# LCD_i2c_Encoder.net
KiCad netlist of a schematic drawn in EAGLE
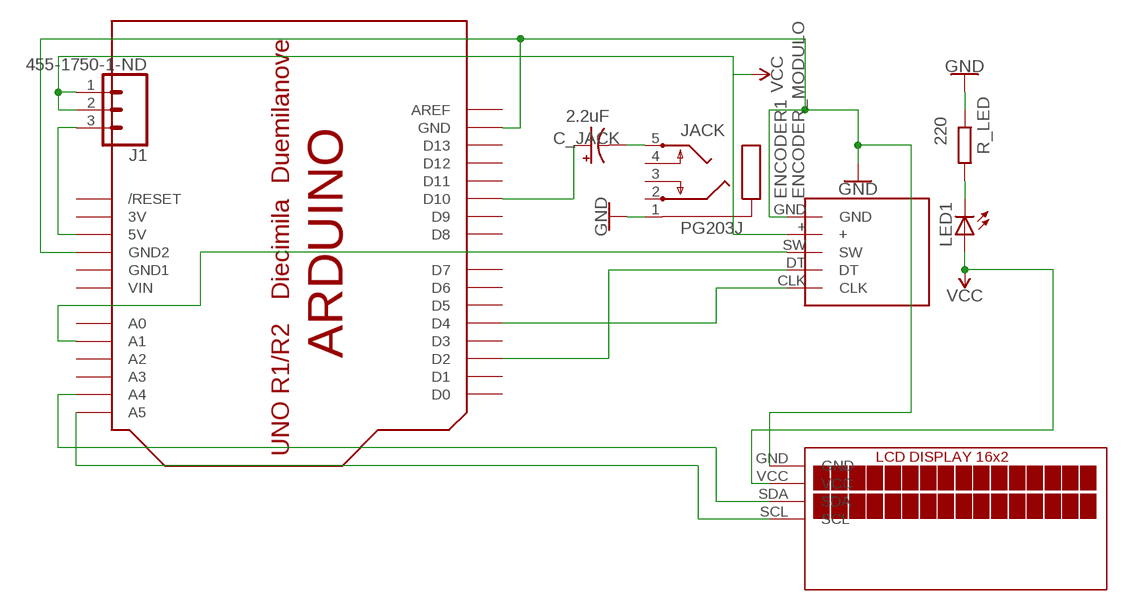
[diagram p0: schematic, sheet 1]

(export (version "E")
  (design (tool "Eeschema 10.0.6"))
  (components
    (comp (ref "C_JACK")
      (value "CPOL-USE2,5-6E")
      (footprint "eagle-import:E2,5-6E")
      (fields (field (name "CAPACITANCIA") "2.2uF"))
      (libsource (lib "eagle-import") (part "CPOL-USE2,5-6E"))
    )
    (comp (ref "ENCODER1")
      (value "ENCODER_MODULO")
      (footprint "eagle-import:ENCODER_MODULO")
      (libsource (lib "eagle-import") (part "ENCODER_MODULO"))
    )
    (comp (ref "J1")
      (value "455-1750-1-ND")
      (footprint "eagle-import:1X03")
      (libsource (lib "eagle-import") (part "CONN_03"))
    )
    (comp (ref "JACK")
      (value "PG203J")
      (footprint "eagle-import:PG203J")
      (libsource (lib "eagle-import") (part "PG203J"))
    )
    (comp (ref "LCD1")
      (value "LCDI2C")
      (footprint "eagle-import:TUXGR_16X2_R2")
      (libsource (lib "eagle-import") (part "LCDI2C"))
    )
    (comp (ref "LED1")
      (value "LED5MM")
      (footprint "eagle-import:LED5MM")
      (libsource (lib "eagle-import") (part "LED5MM"))
    )
    (comp (ref "R_LED")
      (value "R-EU_0204/7")
      (footprint "eagle-import:0204_7")
      (fields (field (name "RESISTENCIA") "220"))
      (libsource (lib "eagle-import") (part "R-EU_0204/7"))
    )
    (comp (ref "U$1")
      (value "ARDUINOUNO")
      (footprint "eagle-import:ARDUINO")
      (libsource (lib "eagle-import") (part "ARDUINOUNO"))
    )
  )
  (nets
    (net (code "1") (name "/3V") (class "Default")
      (node (ref "U$1") (pin "3V") (pinfunction "3V_3V") (pintype "power_in"))
    )
    (net (code "2") (name "/GND1") (class "Default")
      (node (ref "U$1") (pin "GND1") (pinfunction "GND1_GND1") (pintype "power_in"))
    )
    (net (code "3") (name "/VIN") (class "Default")
      (node (ref "U$1") (pin "VIN") (pinfunction "VIN_VIN") (pintype "power_in"))
    )
    (net (code "4") (name "GND") (class "Default")
      (node (ref "ENCODER1") (pin "GND") (pinfunction "GND_GND") (pintype "bidirectional"))
      (node (ref "JACK") (pin "1") (pinfunction "1_1") (pintype "passive"))
      (node (ref "LCD1") (pin "GND") (pinfunction "GND_GND") (pintype "bidirectional"))
      (node (ref "R_LED") (pin "2") (pinfunction "2_2") (pintype "passive"))
      (node (ref "U$1") (pin "GND") (pinfunction "GND_GND") (pintype "power_in"))
      (node (ref "U$1") (pin "GND2") (pinfunction "GND2_GND2") (pintype "power_in"))
    )
    (net (code "5") (name "Net-(C_JACK-Pad+)") (class "Default")
      (node (ref "C_JACK") (pin "+") (pinfunction "+_+") (pintype "passive"))
      (node (ref "U$1") (pin "D10") (pinfunction "D10_D10") (pintype "bidirectional"))
    )
    (net (code "6") (name "Net-(C_JACK-Pad-)") (class "Default")
      (node (ref "C_JACK") (pin "-") (pinfunction "-_-") (pintype "passive"))
      (node (ref "JACK") (pin "5") (pinfunction "5_5") (pintype "passive"))
    )
    (net (code "7") (name "Net-(ENCODER1-PadCLK)") (class "Default")
      (node (ref "ENCODER1") (pin "CLK") (pinfunction "CLK_CLK") (pintype "bidirectional"))
      (node (ref "U$1") (pin "D4") (pinfunction "D4_D4") (pintype "bidirectional"))
    )
    (net (code "8") (name "Net-(ENCODER1-PadDT)") (class "Default")
      (node (ref "ENCODER1") (pin "DT") (pinfunction "DT_DT") (pintype "bidirectional"))
      (node (ref "U$1") (pin "D2") (pinfunction "D2_D2") (pintype "bidirectional"))
    )
    (net (code "9") (name "Net-(ENCODER1-PadSW)") (class "Default")
      (node (ref "ENCODER1") (pin "SW") (pinfunction "SW_SW") (pintype "bidirectional"))
      (node (ref "U$1") (pin "A1") (pinfunction "A1_A1") (pintype "bidirectional"))
    )
    (net (code "10") (name "Net-(J1-Pad3)") (class "Default")
      (node (ref "J1") (pin "3") (pinfunction "3_3") (pintype "passive"))
      (node (ref "U$1") (pin "5V") (pinfunction "5V_5V") (pintype "power_in"))
    )
    (net (code "11") (name "Net-(LCD1-PadSCL)") (class "Default")
      (node (ref "LCD1") (pin "SCL") (pinfunction "SCL_SCL") (pintype "bidirectional"))
      (node (ref "U$1") (pin "A5") (pinfunction "A5_A5") (pintype "bidirectional"))
    )
    (net (code "12") (name "Net-(LCD1-PadSDA)") (class "Default")
      (node (ref "LCD1") (pin "SDA") (pinfunction "SDA_SDA") (pintype "bidirectional"))
      (node (ref "U$1") (pin "A4") (pinfunction "A4_A4") (pintype "bidirectional"))
    )
    (net (code "13") (name "Net-(LED1-C)") (class "Default")
      (node (ref "LED1") (pin "K") (pinfunction "C_K") (pintype "passive"))
      (node (ref "R_LED") (pin "1") (pinfunction "1_1") (pintype "passive"))
    )
    (net (code "14") (name "VCC") (class "Default")
      (node (ref "ENCODER1") (pin "+") (pinfunction "+_+") (pintype "bidirectional"))
      (node (ref "J1") (pin "1") (pinfunction "1_1") (pintype "passive"))
      (node (ref "J1") (pin "2") (pinfunction "2_2") (pintype "passive"))
      (node (ref "LCD1") (pin "VCC") (pinfunction "VCC_VCC") (pintype "bidirectional"))
      (node (ref "LED1") (pin "A") (pinfunction "A_A") (pintype "passive"))
    )
    (net (code "15") (name "unconnected-(JACK-Pad2)") (class "Default")
      (node (ref "JACK") (pin "2") (pinfunction "2_2") (pintype "passive"))
    )
    (net (code "16") (name "unconnected-(JACK-Pad3)") (class "Default")
      (node (ref "JACK") (pin "3") (pinfunction "3_3") (pintype "passive"))
    )
    (net (code "17") (name "unconnected-(JACK-Pad4)") (class "Default")
      (node (ref "JACK") (pin "4") (pinfunction "4_4") (pintype "passive"))
    )
    (net (code "18") (name "unconnected-(U$1-PadA0)") (class "Default")
      (node (ref "U$1") (pin "A0") (pinfunction "A0_A0") (pintype "bidirectional"))
    )
    (net (code "19") (name "unconnected-(U$1-PadA2)") (class "Default")
      (node (ref "U$1") (pin "A2") (pinfunction "A2_A2") (pintype "bidirectional"))
    )
    (net (code "20") (name "unconnected-(U$1-PadA3)") (class "Default")
      (node (ref "U$1") (pin "A3") (pinfunction "A3_A3") (pintype "bidirectional"))
    )
    (net (code "21") (name "unconnected-(U$1-PadAREF)") (class "Default")
      (node (ref "U$1") (pin "AREF") (pinfunction "AREF_AREF") (pintype "bidirectional"))
    )
    (net (code "22") (name "unconnected-(U$1-PadD0)") (class "Default")
      (node (ref "U$1") (pin "D0") (pinfunction "D0_D0") (pintype "bidirectional"))
    )
    (net (code "23") (name "unconnected-(U$1-PadD1)") (class "Default")
      (node (ref "U$1") (pin "D1") (pinfunction "D1_D1") (pintype "bidirectional"))
    )
    (net (code "24") (name "unconnected-(U$1-PadD3)") (class "Default")
      (node (ref "U$1") (pin "D3") (pinfunction "D3_D3") (pintype "bidirectional"))
    )
    (net (code "25") (name "unconnected-(U$1-PadD5)") (class "Default")
      (node (ref "U$1") (pin "D5") (pinfunction "D5_D5") (pintype "bidirectional"))
    )
    (net (code "26") (name "unconnected-(U$1-PadD6)") (class "Default")
      (node (ref "U$1") (pin "D6") (pinfunction "D6_D6") (pintype "bidirectional"))
    )
    (net (code "27") (name "unconnected-(U$1-PadD7)") (class "Default")
      (node (ref "U$1") (pin "D7") (pinfunction "D7_D7") (pintype "bidirectional"))
    )
    (net (code "28") (name "unconnected-(U$1-PadD8)") (class "Default")
      (node (ref "U$1") (pin "D8") (pinfunction "D8_D8") (pintype "bidirectional"))
    )
    (net (code "29") (name "unconnected-(U$1-PadD9)") (class "Default")
      (node (ref "U$1") (pin "D9") (pinfunction "D9_D9") (pintype "bidirectional"))
    )
    (net (code "30") (name "unconnected-(U$1-PadD11)") (class "Default")
      (node (ref "U$1") (pin "D11") (pinfunction "D11_D11") (pintype "bidirectional"))
    )
    (net (code "31") (name "unconnected-(U$1-PadD12)") (class "Default")
      (node (ref "U$1") (pin "D12") (pinfunction "D12_D12") (pintype "bidirectional"))
    )
    (net (code "32") (name "unconnected-(U$1-PadD13)") (class "Default")
      (node (ref "U$1") (pin "D13") (pinfunction "D13_D13") (pintype "bidirectional"))
    )
    (net (code "33") (name "unconnected-(U$1-{slash}RESET-PadRESET)") (class "Default")
      (node (ref "U$1") (pin "RESET") (pinfunction "/RESET_RESET") (pintype "bidirectional"))
    )
  )
)
